# weight_sens.net
KiCad netlist of a schematic drawn in EAGLE
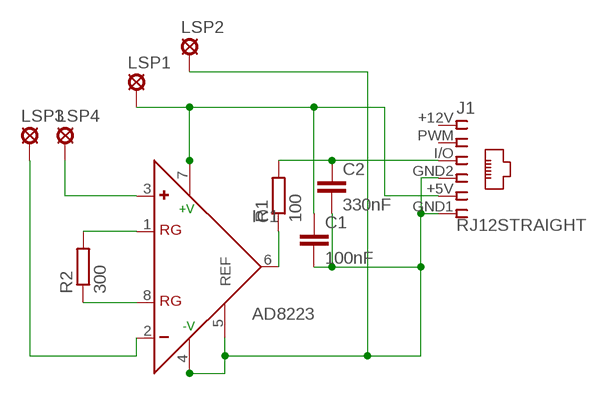
[diagram p0: schematic, sheet 1]

(export (version "E")
  (design (tool "Eeschema 10.0.6"))
  (components
    (comp (ref "C1")
      (value "100nF")
      (footprint "eagle-import:C1206")
      (libsource (lib "eagle-import") (part "C-EUC1206"))
    )
    (comp (ref "C2")
      (value "330nF")
      (footprint "eagle-import:C1206")
      (libsource (lib "eagle-import") (part "C-EUC1206"))
    )
    (comp (ref "IC1")
      (value "AD8223")
      (footprint "eagle-import:SO8")
      (fields (field (name "MPN") "AD620AR"))
      (libsource (lib "eagle-import") (part "AD620R"))
    )
    (comp (ref "J1")
      (value "RJ12STRAIGHT")
      (footprint "eagle-import:RJ12-STRAIGHT")
      (libsource (lib "eagle-import") (part "RJ12STRAIGHT"))
    )
    (comp (ref "LSP1")
      (value "LSP10")
      (footprint "eagle-import:LSP10")
      (libsource (lib "eagle-import") (part "LSP10"))
    )
    (comp (ref "LSP2")
      (value "LSP10")
      (footprint "eagle-import:LSP10")
      (libsource (lib "eagle-import") (part "LSP10"))
    )
    (comp (ref "LSP3")
      (value "LSP10")
      (footprint "eagle-import:LSP10")
      (libsource (lib "eagle-import") (part "LSP10"))
    )
    (comp (ref "LSP4")
      (value "LSP10")
      (footprint "eagle-import:LSP10")
      (libsource (lib "eagle-import") (part "LSP10"))
    )
    (comp (ref "R1")
      (value "100")
      (footprint "eagle-import:R1206")
      (libsource (lib "eagle-import") (part "R-EU_R1206"))
    )
    (comp (ref "R2")
      (value "300")
      (footprint "eagle-import:R1206")
      (libsource (lib "eagle-import") (part "R-EU_R1206"))
    )
  )
  (nets
    (net (code "1") (name "Net-(IC1-+)") (class "Default")
      (node (ref "IC1") (pin "3") (pinfunction "+_3") (pintype "input"))
      (node (ref "LSP4") (pin "MP") (pinfunction "MP_MP") (pintype "passive"))
    )
    (net (code "2") (name "Net-(IC1-+V)") (class "Default")
      (node (ref "C1") (pin "1") (pinfunction "1_1") (pintype "passive"))
      (node (ref "IC1") (pin "7") (pinfunction "+V_7") (pintype "power_in"))
      (node (ref "J1") (pin "+5V") (pinfunction "5_+5V") (pintype "bidirectional"))
      (node (ref "LSP1") (pin "MP") (pinfunction "MP_MP") (pintype "passive"))
    )
    (net (code "3") (name "Net-(IC1--)") (class "Default")
      (node (ref "IC1") (pin "2") (pinfunction "-_2") (pintype "input"))
      (node (ref "LSP3") (pin "MP") (pinfunction "MP_MP") (pintype "passive"))
    )
    (net (code "4") (name "Net-(IC1--V)") (class "Default")
      (node (ref "C1") (pin "2") (pinfunction "2_2") (pintype "passive"))
      (node (ref "C2") (pin "2") (pinfunction "2_2") (pintype "passive"))
      (node (ref "IC1") (pin "4") (pinfunction "-V_4") (pintype "power_in"))
      (node (ref "IC1") (pin "5") (pinfunction "REF_5") (pintype "passive"))
      (node (ref "J1") (pin "GND1") (pinfunction "6_GND1") (pintype "bidirectional"))
      (node (ref "J1") (pin "GND2") (pinfunction "4_GND2") (pintype "bidirectional"))
      (node (ref "LSP2") (pin "MP") (pinfunction "MP_MP") (pintype "passive"))
    )
    (net (code "5") (name "Net-(IC1-OUT)") (class "Default")
      (node (ref "IC1") (pin "6") (pinfunction "OUT_6") (pintype "output"))
      (node (ref "R1") (pin "1") (pinfunction "1_1") (pintype "passive"))
    )
    (net (code "6") (name "Net-(IC1-RG-Pad1)") (class "Default")
      (node (ref "IC1") (pin "1") (pinfunction "RG_1") (pintype "passive"))
      (node (ref "R2") (pin "2") (pinfunction "2_2") (pintype "passive"))
    )
    (net (code "7") (name "Net-(IC1-RG-Pad8)") (class "Default")
      (node (ref "IC1") (pin "8") (pinfunction "RG_8") (pintype "passive"))
      (node (ref "R2") (pin "1") (pinfunction "1_1") (pintype "passive"))
    )
    (net (code "8") (name "Net-(J1-3)") (class "Default")
      (node (ref "C2") (pin "1") (pinfunction "1_1") (pintype "passive"))
      (node (ref "J1") (pin "I/O") (pinfunction "3_I/O") (pintype "bidirectional"))
      (node (ref "R1") (pin "2") (pinfunction "2_2") (pintype "passive"))
    )
    (net (code "9") (name "unconnected-(J1-1-Pad+12V)") (class "Default")
      (node (ref "J1") (pin "+12V") (pinfunction "1_+12V") (pintype "bidirectional"))
    )
    (net (code "10") (name "unconnected-(J1-2-PadPWM)") (class "Default")
      (node (ref "J1") (pin "PWM") (pinfunction "2_PWM") (pintype "bidirectional"))
    )
  )
)
